# SAMV71_Xplained_Ultra_Audio.net
KiCad netlist of a schematic drawn in Altium Designer
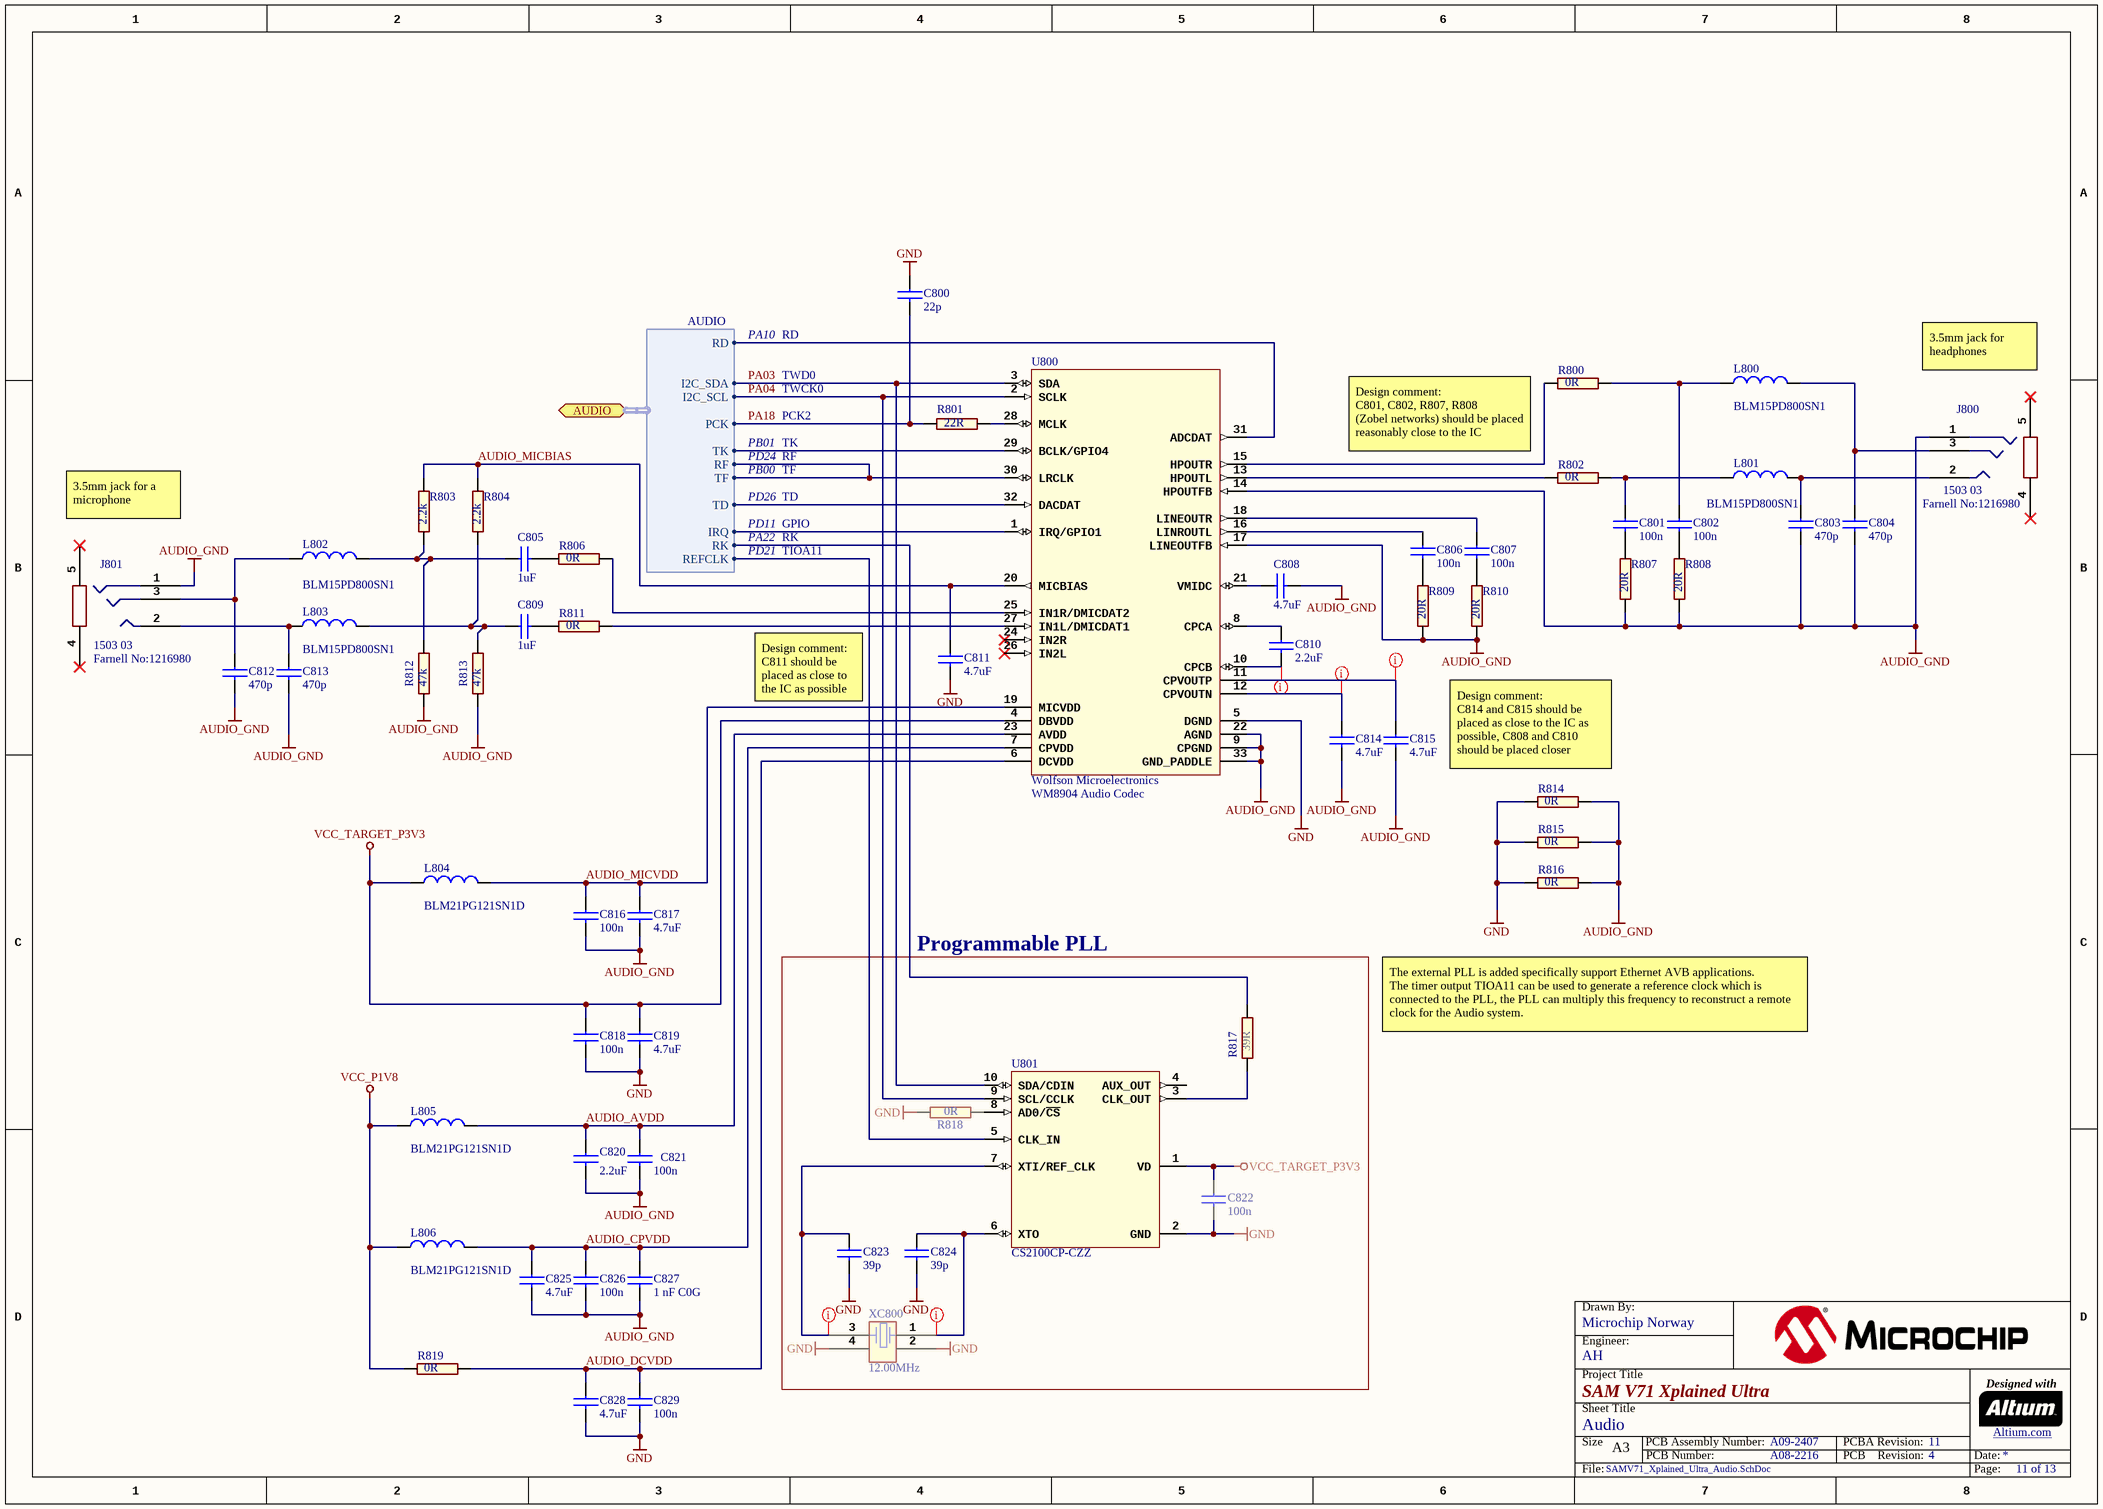
[diagram p0: SAMV71_Xplained_Ultra_Audio.SchDoc]

(export (version "E")
  (design (tool "Eeschema 10.0.6"))
  (components
    (comp (ref "C800")
      (value "22p")
      (footprint "AP1-00001")
      (description "Ceramic capacitor, SMD 0402, NP0, 50V, +/-5%")
      (fields (field (name "TOLERANCE") "50V, +/-5%") (field (name "MANUFACTURER") "YAGEO CORP"))
      (libsource (lib "AltiumDbLib") (part "CAP-NONPOL"))
    )
    (comp (ref "C801")
      (value "100n")
      (footprint "AP1-00001")
      (description "Ceramic capacitor, SMD 0402, X7R, 16V, +/-10%")
      (fields (field (name "TOLERANCE") "16V, +/-10%") (field (name "MANUFACTURER") "Kemet"))
      (libsource (lib "AltiumDbLib") (part "CAP-NONPOL"))
    )
    (comp (ref "C802")
      (value "100n")
      (footprint "AP1-00001")
      (description "Ceramic capacitor, SMD 0402, X7R, 16V, +/-10%")
      (fields (field (name "TOLERANCE") "16V, +/-10%") (field (name "MANUFACTURER") "Kemet"))
      (libsource (lib "AltiumDbLib") (part "CAP-NONPOL"))
    )
    (comp (ref "C803")
      (value "470p")
      (footprint "AP1-00001")
      (description "Ceramic capacitor, SMD 0402, X7R, 50V, +/-10%")
      (fields (field (name "TOLERANCE") "50V, +/-10%") (field (name "MANUFACTURER") "Murata"))
      (libsource (lib "AltiumDbLib") (part "CAP-NONPOL"))
    )
    (comp (ref "C804")
      (value "470p")
      (footprint "AP1-00001")
      (description "Ceramic capacitor, SMD 0402, X7R, 50V, +/-10%")
      (fields (field (name "TOLERANCE") "50V, +/-10%") (field (name "MANUFACTURER") "Murata"))
      (libsource (lib "AltiumDbLib") (part "CAP-NONPOL"))
    )
    (comp (ref "C805")
      (value "1uF")
      (footprint "AP1-00038")
      (description "Ceramic capacitor, SMD 0402, X5R, 10V, ±10 %")
      (fields (field (name "MANUFACTURER") "AVX") (field (name "MPN") "0402ZD105KAT2A"))
      (libsource (lib "AltiumDbLib") (part "CAP-NONPOL"))
    )
    (comp (ref "C806")
      (value "100n")
      (footprint "AP1-00001")
      (description "Ceramic capacitor, SMD 0402, X7R, 16V, +/-10%")
      (fields (field (name "TOLERANCE") "16V, +/-10%") (field (name "MANUFACTURER") "Kemet"))
      (libsource (lib "AltiumDbLib") (part "CAP-NONPOL"))
    )
    (comp (ref "C807")
      (value "100n")
      (footprint "AP1-00001")
      (description "Ceramic capacitor, SMD 0402, X7R, 16V, +/-10%")
      (fields (field (name "TOLERANCE") "16V, +/-10%") (field (name "MANUFACTURER") "Kemet"))
      (libsource (lib "AltiumDbLib") (part "CAP-NONPOL"))
    )
    (comp (ref "C808")
      (value "4.7uF")
      (footprint "AP1-00039")
      (description "Ceramic capacitor, SMD 0603, X5R, 10V, 10% (de31036)")
      (fields (field (name "TOLERANCE") "10%") (field (name "MANUFACTURER") "WALSIN Technology Corporation"))
      (libsource (lib "AltiumDbLib") (part "CAP-NONPOL"))
    )
    (comp (ref "C809")
      (value "1uF")
      (footprint "AP1-00038")
      (description "Ceramic capacitor, SMD 0402, X5R, 10V, ±10 %")
      (fields (field (name "MANUFACTURER") "AVX") (field (name "MPN") "0402ZD105KAT2A"))
      (libsource (lib "AltiumDbLib") (part "CAP-NONPOL"))
    )
    (comp (ref "C810")
      (value "2.2uF")
      (footprint "AP1-00001")
      (description "Ceramic capacitor, SMD 0402, X5R, 6.3V, +/-20%")
      (fields (field (name "TOLERANCE") "Â±20%") (field (name "MANUFACTURER") "Kemet"))
      (libsource (lib "AltiumDbLib") (part "CAP-NONPOL"))
    )
    (comp (ref "C811")
      (value "4.7uF")
      (footprint "AP1-00039")
      (description "Ceramic capacitor, SMD 0603, X5R, 10V, 10% (de31036)")
      (fields (field (name "TOLERANCE") "10%") (field (name "MANUFACTURER") "WALSIN Technology Corporation"))
      (libsource (lib "AltiumDbLib") (part "CAP-NONPOL"))
    )
    (comp (ref "C812")
      (value "470p")
      (footprint "AP1-00001")
      (description "Ceramic capacitor, SMD 0402, X7R, 50V, +/-10%")
      (fields (field (name "TOLERANCE") "50V, +/-10%") (field (name "MANUFACTURER") "Murata"))
      (libsource (lib "AltiumDbLib") (part "CAP-NONPOL"))
    )
    (comp (ref "C813")
      (value "470p")
      (footprint "AP1-00001")
      (description "Ceramic capacitor, SMD 0402, X7R, 50V, +/-10%")
      (fields (field (name "TOLERANCE") "50V, +/-10%") (field (name "MANUFACTURER") "Murata"))
      (libsource (lib "AltiumDbLib") (part "CAP-NONPOL"))
    )
    (comp (ref "C814")
      (value "4.7uF")
      (footprint "AP1-00001")
      (description "Ceramic capacitor, SMD 0402, X5R, 6.3V, +/-20% (de33687)")
      (fields (field (name "TOLERANCE") "+-20%") (field (name "MANUFACTURER") "Murata"))
      (libsource (lib "AltiumDbLib") (part "CAP-NONPOL"))
    )
    (comp (ref "C815")
      (value "4.7uF")
      (footprint "AP1-00001")
      (description "Ceramic capacitor, SMD 0402, X5R, 6.3V, +/-20% (de33687)")
      (fields (field (name "TOLERANCE") "+-20%") (field (name "MANUFACTURER") "Murata"))
      (libsource (lib "AltiumDbLib") (part "CAP-NONPOL"))
    )
    (comp (ref "C816")
      (value "100n")
      (footprint "AP1-00001")
      (description "Ceramic capacitor, SMD 0402, X7R, 16V, +/-10%")
      (fields (field (name "TOLERANCE") "16V, +/-10%") (field (name "MANUFACTURER") "Kemet"))
      (libsource (lib "AltiumDbLib") (part "CAP-NONPOL"))
    )
    (comp (ref "C817")
      (value "4.7uF")
      (footprint "AP1-00039")
      (description "Ceramic capacitor, SMD 0603, X5R, 10V, 10% (de31036)")
      (fields (field (name "TOLERANCE") "10%") (field (name "MANUFACTURER") "WALSIN Technology Corporation"))
      (libsource (lib "AltiumDbLib") (part "CAP-NONPOL"))
    )
    (comp (ref "C818")
      (value "100n")
      (footprint "AP1-00001")
      (description "Ceramic capacitor, SMD 0402, X7R, 16V, +/-10%")
      (fields (field (name "TOLERANCE") "16V, +/-10%") (field (name "MANUFACTURER") "Kemet"))
      (libsource (lib "AltiumDbLib") (part "CAP-NONPOL"))
    )
    (comp (ref "C819")
      (value "4.7uF")
      (footprint "AP1-00039")
      (description "Ceramic capacitor, SMD 0603, X5R, 10V, 10% (de31036)")
      (fields (field (name "TOLERANCE") "10%") (field (name "MANUFACTURER") "WALSIN Technology Corporation"))
      (libsource (lib "AltiumDbLib") (part "CAP-NONPOL"))
    )
    (comp (ref "C820")
      (value "2.2uF")
      (footprint "AP1-00001")
      (description "Ceramic capacitor, SMD 0402, X5R, 6.3V, +/-20%")
      (fields (field (name "TOLERANCE") "Â±20%") (field (name "MANUFACTURER") "Kemet"))
      (libsource (lib "AltiumDbLib") (part "CAP-NONPOL"))
    )
    (comp (ref "C821")
      (value "100n")
      (footprint "AP1-00001")
      (description "Ceramic capacitor, SMD 0402, X7R, 16V, +/-10%")
      (fields (field (name "TOLERANCE") "16V, +/-10%") (field (name "MANUFACTURER") "Kemet"))
      (libsource (lib "AltiumDbLib") (part "CAP-NONPOL"))
    )
    (comp (ref "C822")
      (value "100n")
      (footprint "AP1-00001")
      (description "Ceramic capacitor, SMD 0402, X7R, 16V, +/-10%")
      (fields (field (name "TOLERANCE") "16V, +/-10%") (field (name "MANUFACTURER") "Kemet"))
      (libsource (lib "AltiumDbLib") (part "CAP-NONPOL"))
    )
    (comp (ref "C823")
      (value "39p")
      (footprint "AP1-00001")
      (description "Ceramic capacitor, SMD 0402, NP0, 50V, +/-5%")
      (fields (field (name "TOLERANCE") "50V, +/-5%"))
      (libsource (lib "AltiumDbLib") (part "CAP-NONPOL"))
    )
    (comp (ref "C824")
      (value "39p")
      (footprint "AP1-00001")
      (description "Ceramic capacitor, SMD 0402, NP0, 50V, +/-5%")
      (fields (field (name "TOLERANCE") "50V, +/-5%"))
      (libsource (lib "AltiumDbLib") (part "CAP-NONPOL"))
    )
    (comp (ref "C825")
      (value "4.7uF")
      (footprint "AP1-00039")
      (description "Ceramic capacitor, SMD 0603, X5R, 10V, 10% (de31036)")
      (fields (field (name "TOLERANCE") "10%") (field (name "MANUFACTURER") "WALSIN Technology Corporation"))
      (libsource (lib "AltiumDbLib") (part "CAP-NONPOL"))
    )
    (comp (ref "C826")
      (value "100n")
      (footprint "AP1-00001")
      (description "Ceramic capacitor, SMD 0402, X7R, 16V, +/-10%")
      (fields (field (name "TOLERANCE") "16V, +/-10%") (field (name "MANUFACTURER") "Kemet"))
      (libsource (lib "AltiumDbLib") (part "CAP-NONPOL"))
    )
    (comp (ref "C827")
      (value "1 nF C0G")
      (footprint "AP1-00001")
      (description "Ceramic capacitor, SMD 0402, C0G, 50V, +/-5%")
      (fields (field (name "TOLERANCE") "5%") (field (name "MANUFACTURER") "Murata"))
      (libsource (lib "AltiumDbLib") (part "CAP-NONPOL"))
    )
    (comp (ref "C828")
      (value "4.7uF")
      (footprint "AP1-00039")
      (description "Ceramic capacitor, SMD 0603, X5R, 10V, 10% (de31036)")
      (fields (field (name "TOLERANCE") "10%") (field (name "MANUFACTURER") "WALSIN Technology Corporation"))
      (libsource (lib "AltiumDbLib") (part "CAP-NONPOL"))
    )
    (comp (ref "C829")
      (value "100n")
      (footprint "AP1-00001")
      (description "Ceramic capacitor, SMD 0402, X7R, 16V, +/-10%")
      (fields (field (name "TOLERANCE") "16V, +/-10%") (field (name "MANUFACTURER") "Kemet"))
      (libsource (lib "AltiumDbLib") (part "CAP-NONPOL"))
    )
    (comp (ref "J800")
      (value "Farnell No:1216980")
      (footprint "AP8-00397")
      (description "3.5mm stereo phone jack")
      (fields
        (field (name "ALTIUM_VALUE") "1503 03")
        (field (name "MANUFACTURER") "Lumberg")
        (field (name "MPN") "1503 03")
      )
      (libsource (lib "") (part "Jack_Stereo_1503_03_1"))
    )
    (comp (ref "J801")
      (value "Farnell No:1216980")
      (footprint "AP8-00397")
      (description "3.5mm stereo phone jack")
      (fields
        (field (name "ALTIUM_VALUE") "1503 03")
        (field (name "MANUFACTURER") "Lumberg")
        (field (name "MPN") "1503 03")
      )
      (libsource (lib "AltiumDbLib") (part "Jack_Stereo_1503_03"))
    )
    (comp (ref "L800")
      (value "BLM15PD800SN1")
      (footprint "AP3-00028")
      (description "FERRITE CHIP 80 OHM 1500MA 0402")
      (fields (field (name "TOLERANCE") "±25%") (field (name "MANUFACTURER") "Murata"))
      (libsource (lib "AltiumDbLib") (part "INDUCTOR"))
    )
    (comp (ref "L801")
      (value "BLM15PD800SN1")
      (footprint "AP3-00028")
      (description "FERRITE CHIP 80 OHM 1500MA 0402")
      (fields (field (name "TOLERANCE") "±25%") (field (name "MANUFACTURER") "Murata"))
      (libsource (lib "AltiumDbLib") (part "INDUCTOR"))
    )
    (comp (ref "L802")
      (value "BLM15PD800SN1")
      (footprint "AP3-00028")
      (description "FERRITE CHIP 80 OHM 1500MA 0402")
      (fields (field (name "TOLERANCE") "±25%") (field (name "MANUFACTURER") "Murata"))
      (libsource (lib "AltiumDbLib") (part "INDUCTOR"))
    )
    (comp (ref "L803")
      (value "BLM15PD800SN1")
      (footprint "AP3-00028")
      (description "FERRITE CHIP 80 OHM 1500MA 0402")
      (fields (field (name "TOLERANCE") "±25%") (field (name "MANUFACTURER") "Murata"))
      (libsource (lib "AltiumDbLib") (part "INDUCTOR"))
    )
    (comp (ref "L804")
      (value "BLM21PG121SN1D")
      (footprint "AP3-00104")
      (fields (field (name "MANUFACTURER") "Murata"))
      (libsource (lib "AltiumDbLib") (part "INDUCTOR"))
    )
    (comp (ref "L805")
      (value "BLM21PG121SN1D")
      (footprint "AP3-00104")
      (fields (field (name "MANUFACTURER") "Murata"))
      (libsource (lib "AltiumDbLib") (part "INDUCTOR"))
    )
    (comp (ref "L806")
      (value "BLM21PG121SN1D")
      (footprint "AP3-00104")
      (fields (field (name "MANUFACTURER") "Murata"))
      (libsource (lib "AltiumDbLib") (part "INDUCTOR"))
    )
    (comp (ref "R800")
      (value "0R")
      (footprint "AP2-00000")
      (description "RES 0.0 OHM 1/16W 0402 SMD")
      (fields (field (name "TOLERANCE") "1 %") (field (name "MANUFACTURER") "(n/a)"))
      (libsource (lib "AltiumDbLib") (part "R2"))
    )
    (comp (ref "R801")
      (value "22R")
      (footprint "AP2-00000")
      (description "Thick film resistor, SMD 0402, 1/16W, 1% (de23607)")
      (fields (field (name "TOLERANCE") "1 %") (field (name "MANUFACTURER") "Samsung"))
      (libsource (lib "AltiumDbLib") (part "R2"))
    )
    (comp (ref "R802")
      (value "0R")
      (footprint "AP2-00000")
      (description "RES 0.0 OHM 1/16W 0402 SMD")
      (fields (field (name "TOLERANCE") "1 %") (field (name "MANUFACTURER") "(n/a)"))
      (libsource (lib "AltiumDbLib") (part "R2"))
    )
    (comp (ref "R803")
      (value "2.2k")
      (footprint "AP2-00000")
      (description "Thick film resistor, SMD 0402, 1/16W, 1%")
      (fields (field (name "TOLERANCE") "1 %") (field (name "MANUFACTURER") "ASJ"))
      (libsource (lib "") (part "R2_1"))
    )
    (comp (ref "R804")
      (value "2.2k")
      (footprint "AP2-00000")
      (description "Thick film resistor, SMD 0402, 1/16W, 1%")
      (fields (field (name "TOLERANCE") "1 %") (field (name "MANUFACTURER") "ASJ"))
      (libsource (lib "") (part "R2_1"))
    )
    (comp (ref "R806")
      (value "0R")
      (footprint "AP2-00000")
      (description "RES 0.0 OHM 1/16W 0402 SMD")
      (fields (field (name "TOLERANCE") "1 %") (field (name "MANUFACTURER") "(n/a)"))
      (libsource (lib "AltiumDbLib") (part "R2"))
    )
    (comp (ref "R807")
      (value "20R")
      (footprint "AP2-00000")
      (description "Thick film resistor, SMD 0402, 1/16W, 1%")
      (fields (field (name "TOLERANCE") "1 %") (field (name "MANUFACTURER") "vishay"))
      (libsource (lib "") (part "R2_1"))
    )
    (comp (ref "R808")
      (value "20R")
      (footprint "AP2-00000")
      (description "Thick film resistor, SMD 0402, 1/16W, 1%")
      (fields (field (name "TOLERANCE") "1 %") (field (name "MANUFACTURER") "vishay"))
      (libsource (lib "") (part "R2_1"))
    )
    (comp (ref "R809")
      (value "20R")
      (footprint "AP2-00000")
      (description "Thick film resistor, SMD 0402, 1/16W, 1%")
      (fields (field (name "TOLERANCE") "1 %") (field (name "MANUFACTURER") "vishay"))
      (libsource (lib "") (part "R2_1"))
    )
    (comp (ref "R810")
      (value "20R")
      (footprint "AP2-00000")
      (description "Thick film resistor, SMD 0402, 1/16W, 1%")
      (fields (field (name "TOLERANCE") "1 %") (field (name "MANUFACTURER") "vishay"))
      (libsource (lib "") (part "R2_1"))
    )
    (comp (ref "R811")
      (value "0R")
      (footprint "AP2-00000")
      (description "RES 0.0 OHM 1/16W 0402 SMD")
      (fields (field (name "TOLERANCE") "1 %") (field (name "MANUFACTURER") "(n/a)"))
      (libsource (lib "AltiumDbLib") (part "R2"))
    )
    (comp (ref "R812")
      (value "47k")
      (footprint "AP2-00000")
      (description "Thick film resistor, SMD 0402, 1/16W, 1%")
      (fields (field (name "TOLERANCE") "1 %") (field (name "MANUFACTURER") "KOA"))
      (libsource (lib "") (part "R2_1"))
    )
    (comp (ref "R813")
      (value "47k")
      (footprint "AP2-00000")
      (description "Thick film resistor, SMD 0402, 1/16W, 1%")
      (fields (field (name "TOLERANCE") "1 %") (field (name "MANUFACTURER") "KOA"))
      (libsource (lib "") (part "R2_1"))
    )
    (comp (ref "R814")
      (value "0R")
      (footprint "AP2-00000")
      (description "RES 0.0 OHM 1/16W 0402 SMD")
      (fields (field (name "TOLERANCE") "1 %") (field (name "MANUFACTURER") "(n/a)"))
      (libsource (lib "AltiumDbLib") (part "R2"))
    )
    (comp (ref "R815")
      (value "0R")
      (footprint "AP2-00000")
      (description "RES 0.0 OHM 1/16W 0402 SMD")
      (fields (field (name "TOLERANCE") "1 %") (field (name "MANUFACTURER") "(n/a)"))
      (libsource (lib "AltiumDbLib") (part "R2"))
    )
    (comp (ref "R816")
      (value "0R")
      (footprint "AP2-00000")
      (description "RES 0.0 OHM 1/16W 0402 SMD")
      (fields (field (name "TOLERANCE") "1 %") (field (name "MANUFACTURER") "(n/a)"))
      (libsource (lib "AltiumDbLib") (part "R2"))
    )
    (comp (ref "R817")
      (value "39R")
      (footprint "AP2-00000")
      (description "Thick film resistor, SMD 0402, 1/16W, 1%")
      (fields (field (name "TOLERANCE") "1 %") (field (name "MANUFACTURER") "ASJ"))
      (libsource (lib "") (part "R2_1"))
    )
    (comp (ref "R818")
      (value "0R")
      (footprint "AP2-00000")
      (description "RES 0.0 OHM 1/16W 0402 SMD")
      (fields (field (name "TOLERANCE") "1 %") (field (name "MANUFACTURER") "(n/a)"))
      (libsource (lib "AltiumDbLib") (part "R2"))
    )
    (comp (ref "R819")
      (value "0R")
      (footprint "AP2-00000")
      (description "RES 0.0 OHM 1/16W 0402 SMD")
      (fields (field (name "TOLERANCE") "1 %") (field (name "MANUFACTURER") "(n/a)"))
      (libsource (lib "AltiumDbLib") (part "R2"))
    )
    (comp (ref "U800")
      (value "Wolfson Microelectronics")
      (footprint "AP6-00420")
      (description "Ultra Low Power Codec for Portable Audio Applications")
      (fields
        (field (name "ALTIUM_VALUE") "WM8904 Audio Codec")
        (field (name "MANUFACTURER") "Wolfson microelectronics")
        (field (name "MPN") "WM8904CGEFL/RV")
      )
      (libsource (lib "AltiumDbLib") (part "WM8904"))
    )
    (comp (ref "U801")
      (value "CS2100CP-CZZ")
      (footprint "AP6-00097")
      (description "Programmable Phase-Locked Loop Clock Generator")
      (fields (field (name "MANUFACTURER") "CIRRUS LOGIC") (field (name "MPN") "CS2100CP-CZZR"))
      (libsource (lib "AltiumDbLib") (part "CS2100"))
    )
    (comp (ref "XC800")
      (value "12.00MHz")
      (footprint "AP7-00039")
      (description "Fox FQ5032B 12.0MHz SMD crystal 738B-12")
      (fields (field (name "TOLERANCE") "Â±30ppm") (field (name "MANUFACTURER") "Fox  Electronics"))
      (libsource (lib "AltiumDbLib") (part "CRYSTAL1324"))
    )
  )
  (nets
    (net (code "2") (name "/AUDIO_AVDD") (class "Default")
      (node (ref "C820") (pin "1") (pinfunction "1_1") (pintype "passive"))
      (node (ref "C821") (pin "1") (pinfunction "1_1") (pintype "passive"))
      (node (ref "L805") (pin "2") (pinfunction "2_2") (pintype "passive"))
      (node (ref "U800") (pin "23") (pinfunction "AVDD_23") (pintype "power_in"))
    )
    (net (code "3") (name "/AUDIO_CPVDD") (class "Default")
      (node (ref "C825") (pin "1") (pinfunction "1_1") (pintype "passive"))
      (node (ref "C826") (pin "1") (pinfunction "1_1") (pintype "passive"))
      (node (ref "C827") (pin "1") (pinfunction "1_1") (pintype "passive"))
      (node (ref "L806") (pin "2") (pinfunction "2_2") (pintype "passive"))
      (node (ref "U800") (pin "7") (pinfunction "CPVDD_7") (pintype "power_in"))
    )
    (net (code "4") (name "/AUDIO_DCVDD") (class "Default")
      (node (ref "C828") (pin "1") (pinfunction "1_1") (pintype "passive"))
      (node (ref "C829") (pin "1") (pinfunction "1_1") (pintype "passive"))
      (node (ref "R819") (pin "2") (pinfunction "2_2") (pintype "passive"))
      (node (ref "U800") (pin "6") (pinfunction "DCVDD_6") (pintype "power_in"))
    )
    (net (code "5") (name "/AUDIO_MICBIAS") (class "Default")
      (node (ref "C811") (pin "1") (pinfunction "1_1") (pintype "passive"))
      (node (ref "R803") (pin "2") (pinfunction "2_2") (pintype "passive"))
      (node (ref "R804") (pin "2") (pinfunction "2_2") (pintype "passive"))
      (node (ref "U800") (pin "20") (pinfunction "MICBIAS_20") (pintype "output"))
    )
    (net (code "6") (name "/AUDIO_MICVDD") (class "Default")
      (node (ref "C816") (pin "1") (pinfunction "1_1") (pintype "passive"))
      (node (ref "C817") (pin "1") (pinfunction "1_1") (pintype "passive"))
      (node (ref "L804") (pin "2") (pinfunction "2_2") (pintype "passive"))
      (node (ref "U800") (pin "19") (pinfunction "MICVDD_19") (pintype "power_in"))
    )
    (net (code "7") (name "/IRQ") (class "Default")
      (node (ref "U800") (pin "1") (pinfunction "IRQ/GPIO1_1") (pintype "bidirectional"))
    )
    (net (code "8") (name "/PA03") (class "Default")
      (node (ref "U800") (pin "3") (pinfunction "SDA_3") (pintype "bidirectional"))
      (node (ref "U801") (pin "10") (pinfunction "SDA/CDIN_10") (pintype "bidirectional"))
    )
    (net (code "9") (name "/PA04") (class "Default")
      (node (ref "U800") (pin "2") (pinfunction "SCLK_2") (pintype "input"))
      (node (ref "U801") (pin "9") (pinfunction "SCL/CCLK_9") (pintype "input"))
    )
    (net (code "10") (name "/PA18") (class "Default")
      (node (ref "C800") (pin "2") (pinfunction "2_2") (pintype "passive"))
      (node (ref "R801") (pin "1") (pinfunction "1_1") (pintype "passive"))
    )
    (net (code "11") (name "/RD") (class "Default")
      (node (ref "U800") (pin "31") (pinfunction "ADCDAT_31") (pintype "output"))
    )
    (net (code "12") (name "/REFCLK") (class "Default")
      (node (ref "U801") (pin "5") (pinfunction "CLK_IN_5") (pintype "input"))
    )
    (net (code "13") (name "/RF") (class "Default")
      (node (ref "U800") (pin "30") (pinfunction "LRCLK_30") (pintype "bidirectional"))
    )
    (net (code "14") (name "/RK") (class "Default")
      (node (ref "R817") (pin "2") (pinfunction "2_2") (pintype "passive"))
    )
    (net (code "15") (name "/TD") (class "Default")
      (node (ref "U800") (pin "32") (pinfunction "DACDAT_32") (pintype "input"))
    )
    (net (code "16") (name "/TK") (class "Default")
      (node (ref "U800") (pin "29") (pinfunction "BCLK/GPIO4_29") (pintype "bidirectional"))
    )
    (net (code "18") (name "AUDIO_GND") (class "Default")
      (node (ref "C803") (pin "2") (pinfunction "2_2") (pintype "passive"))
      (node (ref "C804") (pin "2") (pinfunction "2_2") (pintype "passive"))
      (node (ref "C808") (pin "2") (pinfunction "2_2") (pintype "passive"))
      (node (ref "C812") (pin "2") (pinfunction "2_2") (pintype "passive"))
      (node (ref "C813") (pin "2") (pinfunction "2_2") (pintype "passive"))
      (node (ref "C814") (pin "2") (pinfunction "2_2") (pintype "passive"))
      (node (ref "C815") (pin "2") (pinfunction "2_2") (pintype "passive"))
      (node (ref "C816") (pin "2") (pinfunction "2_2") (pintype "passive"))
      (node (ref "C817") (pin "2") (pinfunction "2_2") (pintype "passive"))
      (node (ref "C820") (pin "2") (pinfunction "2_2") (pintype "passive"))
      (node (ref "C821") (pin "2") (pinfunction "2_2") (pintype "passive"))
      (node (ref "C825") (pin "2") (pinfunction "2_2") (pintype "passive"))
      (node (ref "C826") (pin "2") (pinfunction "2_2") (pintype "passive"))
      (node (ref "C827") (pin "2") (pinfunction "2_2") (pintype "passive"))
      (node (ref "J800") (pin "1") (pinfunction "GND_1") (pintype "passive"))
      (node (ref "J801") (pin "1") (pinfunction "GND_1") (pintype "passive"))
      (node (ref "R807") (pin "1") (pinfunction "1_1") (pintype "passive"))
      (node (ref "R808") (pin "1") (pinfunction "1_1") (pintype "passive"))
      (node (ref "R809") (pin "1") (pinfunction "1_1") (pintype "passive"))
      (node (ref "R810") (pin "1") (pinfunction "1_1") (pintype "passive"))
      (node (ref "R812") (pin "1") (pinfunction "1_1") (pintype "passive"))
      (node (ref "R813") (pin "1") (pinfunction "1_1") (pintype "passive"))
      (node (ref "R814") (pin "2") (pinfunction "2_2") (pintype "passive"))
      (node (ref "R815") (pin "2") (pinfunction "2_2") (pintype "passive"))
      (node (ref "R816") (pin "2") (pinfunction "2_2") (pintype "passive"))
      (node (ref "U800") (pin "14") (pinfunction "HPOUTFB_14") (pintype "input"))
      (node (ref "U800") (pin "17") (pinfunction "LINEOUTFB_17") (pintype "input"))
      (node (ref "U800") (pin "22") (pinfunction "AGND_22") (pintype "power_in"))
      (node (ref "U800") (pin "33") (pinfunction "GND_PADDLE_33") (pintype "power_in"))
      (node (ref "U800") (pin "9") (pinfunction "CPGND_9") (pintype "power_in"))
    )
    (net (code "19") (name "GND") (class "Default")
      (node (ref "C800") (pin "1") (pinfunction "1_1") (pintype "passive"))
      (node (ref "C811") (pin "2") (pinfunction "2_2") (pintype "passive"))
      (node (ref "C818") (pin "2") (pinfunction "2_2") (pintype "passive"))
      (node (ref "C819") (pin "2") (pinfunction "2_2") (pintype "passive"))
      (node (ref "C822") (pin "2") (pinfunction "2_2") (pintype "passive"))
      (node (ref "C823") (pin "2") (pinfunction "2_2") (pintype "passive"))
      (node (ref "C824") (pin "2") (pinfunction "2_2") (pintype "passive"))
      (node (ref "C828") (pin "2") (pinfunction "2_2") (pintype "passive"))
      (node (ref "C829") (pin "2") (pinfunction "2_2") (pintype "passive"))
      (node (ref "R814") (pin "1") (pinfunction "1_1") (pintype "passive"))
      (node (ref "R815") (pin "1") (pinfunction "1_1") (pintype "passive"))
      (node (ref "R816") (pin "1") (pinfunction "1_1") (pintype "passive"))
      (node (ref "R818") (pin "1") (pinfunction "1_1") (pintype "passive"))
      (node (ref "U800") (pin "5") (pinfunction "DGND_5") (pintype "power_in"))
      (node (ref "U801") (pin "2") (pinfunction "GND_2") (pintype "power_in"))
      (node (ref "XC800") (pin "2") (pinfunction "2_2") (pintype "passive"))
      (node (ref "XC800") (pin "4") (pinfunction "4_4") (pintype "passive"))
    )
    (net (code "20") (name "Net-(C801-Pad1)") (class "Default")
      (node (ref "C801") (pin "1") (pinfunction "1_1") (pintype "passive"))
      (node (ref "L801") (pin "1") (pinfunction "1_1") (pintype "passive"))
      (node (ref "R802") (pin "2") (pinfunction "2_2") (pintype "passive"))
    )
    (net (code "21") (name "Net-(C801-Pad2)") (class "Default")
      (node (ref "C801") (pin "2") (pinfunction "2_2") (pintype "passive"))
      (node (ref "R807") (pin "2") (pinfunction "2_2") (pintype "passive"))
    )
    (net (code "22") (name "Net-(C802-Pad1)") (class "Default")
      (node (ref "C802") (pin "1") (pinfunction "1_1") (pintype "passive"))
      (node (ref "L800") (pin "1") (pinfunction "1_1") (pintype "passive"))
      (node (ref "R800") (pin "2") (pinfunction "2_2") (pintype "passive"))
    )
    (net (code "23") (name "Net-(C802-Pad2)") (class "Default")
      (node (ref "C802") (pin "2") (pinfunction "2_2") (pintype "passive"))
      (node (ref "R808") (pin "2") (pinfunction "2_2") (pintype "passive"))
    )
    (net (code "24") (name "Net-(C803-Pad1)") (class "Default")
      (node (ref "C803") (pin "1") (pinfunction "1_1") (pintype "passive"))
      (node (ref "J800") (pin "2") (pintype "passive"))
      (node (ref "L801") (pin "2") (pinfunction "2_2") (pintype "passive"))
    )
    (net (code "25") (name "Net-(C804-Pad1)") (class "Default")
      (node (ref "C804") (pin "1") (pinfunction "1_1") (pintype "passive"))
      (node (ref "J800") (pin "3") (pintype "passive"))
      (node (ref "L800") (pin "2") (pinfunction "2_2") (pintype "passive"))
    )
    (net (code "26") (name "Net-(C805-Pad1)") (class "Default")
      (node (ref "C805") (pin "1") (pinfunction "1_1") (pintype "passive"))
      (node (ref "L802") (pin "2") (pinfunction "2_2") (pintype "passive"))
      (node (ref "R803") (pin "1") (pinfunction "1_1") (pintype "passive"))
      (node (ref "R812") (pin "2") (pinfunction "2_2") (pintype "passive"))
    )
    (net (code "27") (name "Net-(C805-Pad2)") (class "Default")
      (node (ref "C805") (pin "2") (pinfunction "2_2") (pintype "passive"))
      (node (ref "R806") (pin "1") (pinfunction "1_1") (pintype "passive"))
    )
    (net (code "28") (name "Net-(C806-Pad2)") (class "Default")
      (node (ref "C806") (pin "2") (pinfunction "2_2") (pintype "passive"))
      (node (ref "R809") (pin "2") (pinfunction "2_2") (pintype "passive"))
    )
    (net (code "29") (name "Net-(C807-Pad2)") (class "Default")
      (node (ref "C807") (pin "2") (pinfunction "2_2") (pintype "passive"))
      (node (ref "R810") (pin "2") (pinfunction "2_2") (pintype "passive"))
    )
    (net (code "30") (name "Net-(C809-Pad1)") (class "Default")
      (node (ref "C809") (pin "1") (pinfunction "1_1") (pintype "passive"))
      (node (ref "L803") (pin "2") (pinfunction "2_2") (pintype "passive"))
      (node (ref "R804") (pin "1") (pinfunction "1_1") (pintype "passive"))
      (node (ref "R813") (pin "2") (pinfunction "2_2") (pintype "passive"))
    )
    (net (code "31") (name "Net-(C809-Pad2)") (class "Default")
      (node (ref "C809") (pin "2") (pinfunction "2_2") (pintype "passive"))
      (node (ref "R811") (pin "1") (pinfunction "1_1") (pintype "passive"))
    )
    (net (code "32") (name "Net-(C812-Pad1)") (class "Default")
      (node (ref "C812") (pin "1") (pinfunction "1_1") (pintype "passive"))
      (node (ref "J801") (pin "3") (pintype "passive"))
      (node (ref "L802") (pin "1") (pinfunction "1_1") (pintype "passive"))
    )
    (net (code "33") (name "Net-(C813-Pad1)") (class "Default")
      (node (ref "C813") (pin "1") (pinfunction "1_1") (pintype "passive"))
      (node (ref "J801") (pin "2") (pintype "passive"))
      (node (ref "L803") (pin "1") (pinfunction "1_1") (pintype "passive"))
    )
    (net (code "34") (name "Net-(U800-CPCA)") (class "Default")
      (node (ref "C810") (pin "1") (pinfunction "1_1") (pintype "passive"))
      (node (ref "U800") (pin "8") (pinfunction "CPCA_8") (pintype "bidirectional"))
    )
    (net (code "35") (name "Net-(U800-CPCB)") (class "Default")
      (node (ref "C810") (pin "2") (pinfunction "2_2") (pintype "passive"))
      (node (ref "U800") (pin "10") (pinfunction "CPCB_10") (pintype "bidirectional"))
    )
    (net (code "36") (name "Net-(U800-CPVOUTN)") (class "Default")
      (node (ref "C814") (pin "1") (pinfunction "1_1") (pintype "passive"))
      (node (ref "U800") (pin "12") (pinfunction "CPVOUTN_12") (pintype "passive"))
    )
    (net (code "37") (name "Net-(U800-CPVOUTP)") (class "Default")
      (node (ref "C815") (pin "1") (pinfunction "1_1") (pintype "passive"))
      (node (ref "U800") (pin "11") (pinfunction "CPVOUTP_11") (pintype "passive"))
    )
    (net (code "38") (name "Net-(U800-HPOUTL)") (class "Default")
      (node (ref "R802") (pin "1") (pinfunction "1_1") (pintype "passive"))
      (node (ref "U800") (pin "13") (pinfunction "HPOUTL_13") (pintype "output"))
    )
    (net (code "39") (name "Net-(U800-HPOUTR)") (class "Default")
      (node (ref "R800") (pin "1") (pinfunction "1_1") (pintype "passive"))
      (node (ref "U800") (pin "15") (pinfunction "HPOUTR_15") (pintype "output"))
    )
    (net (code "40") (name "Net-(U800-IN1L{slash}DMICDAT1)") (class "Default")
      (node (ref "R811") (pin "2") (pinfunction "2_2") (pintype "passive"))
      (node (ref "U800") (pin "27") (pinfunction "IN1L/DMICDAT1_27") (pintype "input"))
    )
    (net (code "41") (name "Net-(U800-IN1R{slash}DMICDAT2)") (class "Default")
      (node (ref "R806") (pin "2") (pinfunction "2_2") (pintype "passive"))
      (node (ref "U800") (pin "25") (pinfunction "IN1R/DMICDAT2_25") (pintype "input"))
    )
    (net (code "42") (name "Net-(U800-LINEOUTR)") (class "Default")
      (node (ref "C807") (pin "1") (pinfunction "1_1") (pintype "passive"))
      (node (ref "U800") (pin "18") (pinfunction "LINEOUTR_18") (pintype "output"))
    )
    (net (code "43") (name "Net-(U800-LINROUTL)") (class "Default")
      (node (ref "C806") (pin "1") (pinfunction "1_1") (pintype "passive"))
      (node (ref "U800") (pin "16") (pinfunction "LINROUTL_16") (pintype "output"))
    )
    (net (code "44") (name "Net-(U800-MCLK)") (class "Default")
      (node (ref "R801") (pin "2") (pinfunction "2_2") (pintype "passive"))
      (node (ref "U800") (pin "28") (pinfunction "MCLK_28") (pintype "bidirectional"))
    )
    (net (code "45") (name "Net-(U800-VMIDC)") (class "Default")
      (node (ref "C808") (pin "1") (pinfunction "1_1") (pintype "passive"))
      (node (ref "U800") (pin "21") (pinfunction "VMIDC_21") (pintype "bidirectional"))
    )
    (net (code "46") (name "Net-(U801-AD0{slash}~{CS})") (class "Default")
      (node (ref "R818") (pin "2") (pinfunction "2_2") (pintype "passive"))
      (node (ref "U801") (pin "8") (pinfunction "AD0/~{CS}_8") (pintype "input"))
    )
    (net (code "47") (name "Net-(U801-CLK_OUT)") (class "Default")
      (node (ref "R817") (pin "1") (pinfunction "1_1") (pintype "passive"))
      (node (ref "U801") (pin "3") (pinfunction "CLK_OUT_3") (pintype "output"))
    )
    (net (code "48") (name "Net-(U801-XTI{slash}REF_CLK)") (class "Default")
      (node (ref "C823") (pin "1") (pinfunction "1_1") (pintype "passive"))
      (node (ref "U801") (pin "7") (pinfunction "XTI/REF_CLK_7") (pintype "bidirectional"))
      (node (ref "XC800") (pin "3") (pinfunction "3_3") (pintype "passive"))
    )
    (net (code "49") (name "Net-(U801-XTO)") (class "Default")
      (node (ref "C824") (pin "1") (pinfunction "1_1") (pintype "passive"))
      (node (ref "U801") (pin "6") (pinfunction "XTO_6") (pintype "bidirectional"))
      (node (ref "XC800") (pin "1") (pinfunction "1_1") (pintype "passive"))
    )
    (net (code "50") (name "VCC_P1V8") (class "Default")
      (node (ref "L805") (pin "1") (pinfunction "1_1") (pintype "passive"))
      (node (ref "L806") (pin "1") (pinfunction "1_1") (pintype "passive"))
      (node (ref "R819") (pin "1") (pinfunction "1_1") (pintype "passive"))
    )
    (net (code "51") (name "VCC_TARGET_P3V3") (class "Default")
      (node (ref "C818") (pin "1") (pinfunction "1_1") (pintype "passive"))
      (node (ref "C819") (pin "1") (pinfunction "1_1") (pintype "passive"))
      (node (ref "C822") (pin "1") (pinfunction "1_1") (pintype "passive"))
      (node (ref "L804") (pin "1") (pinfunction "1_1") (pintype "passive"))
      (node (ref "U800") (pin "4") (pinfunction "DBVDD_4") (pintype "power_in"))
      (node (ref "U801") (pin "1") (pinfunction "VD_1") (pintype "power_in"))
    )
    (net (code "52") (name "unconnected-(J800-Pad4)") (class "Default")
      (node (ref "J800") (pin "4") (pintype "passive+no_connect"))
    )
    (net (code "53") (name "unconnected-(J800-Pad5)") (class "Default")
      (node (ref "J800") (pin "5") (pintype "passive+no_connect"))
    )
    (net (code "54") (name "unconnected-(J801-Pad4)") (class "Default")
      (node (ref "J801") (pin "4") (pintype "passive+no_connect"))
    )
    (net (code "55") (name "unconnected-(J801-Pad5)") (class "Default")
      (node (ref "J801") (pin "5") (pintype "passive+no_connect"))
    )
    (net (code "56") (name "unconnected-(U800-IN2L-Pad26)") (class "Default")
      (node (ref "U800") (pin "26") (pinfunction "IN2L_26") (pintype "input+no_connect"))
    )
    (net (code "57") (name "unconnected-(U800-IN2R-Pad24)") (class "Default")
      (node (ref "U800") (pin "24") (pinfunction "IN2R_24") (pintype "input+no_connect"))
    )
    (net (code "58") (name "unconnected-(U801-AUX_OUT-Pad4)") (class "Default")
      (node (ref "U801") (pin "4") (pinfunction "AUX_OUT_4") (pintype "output"))
    )
  )
)
